# air.net
KiCad netlist of a schematic drawn in Altium Designer
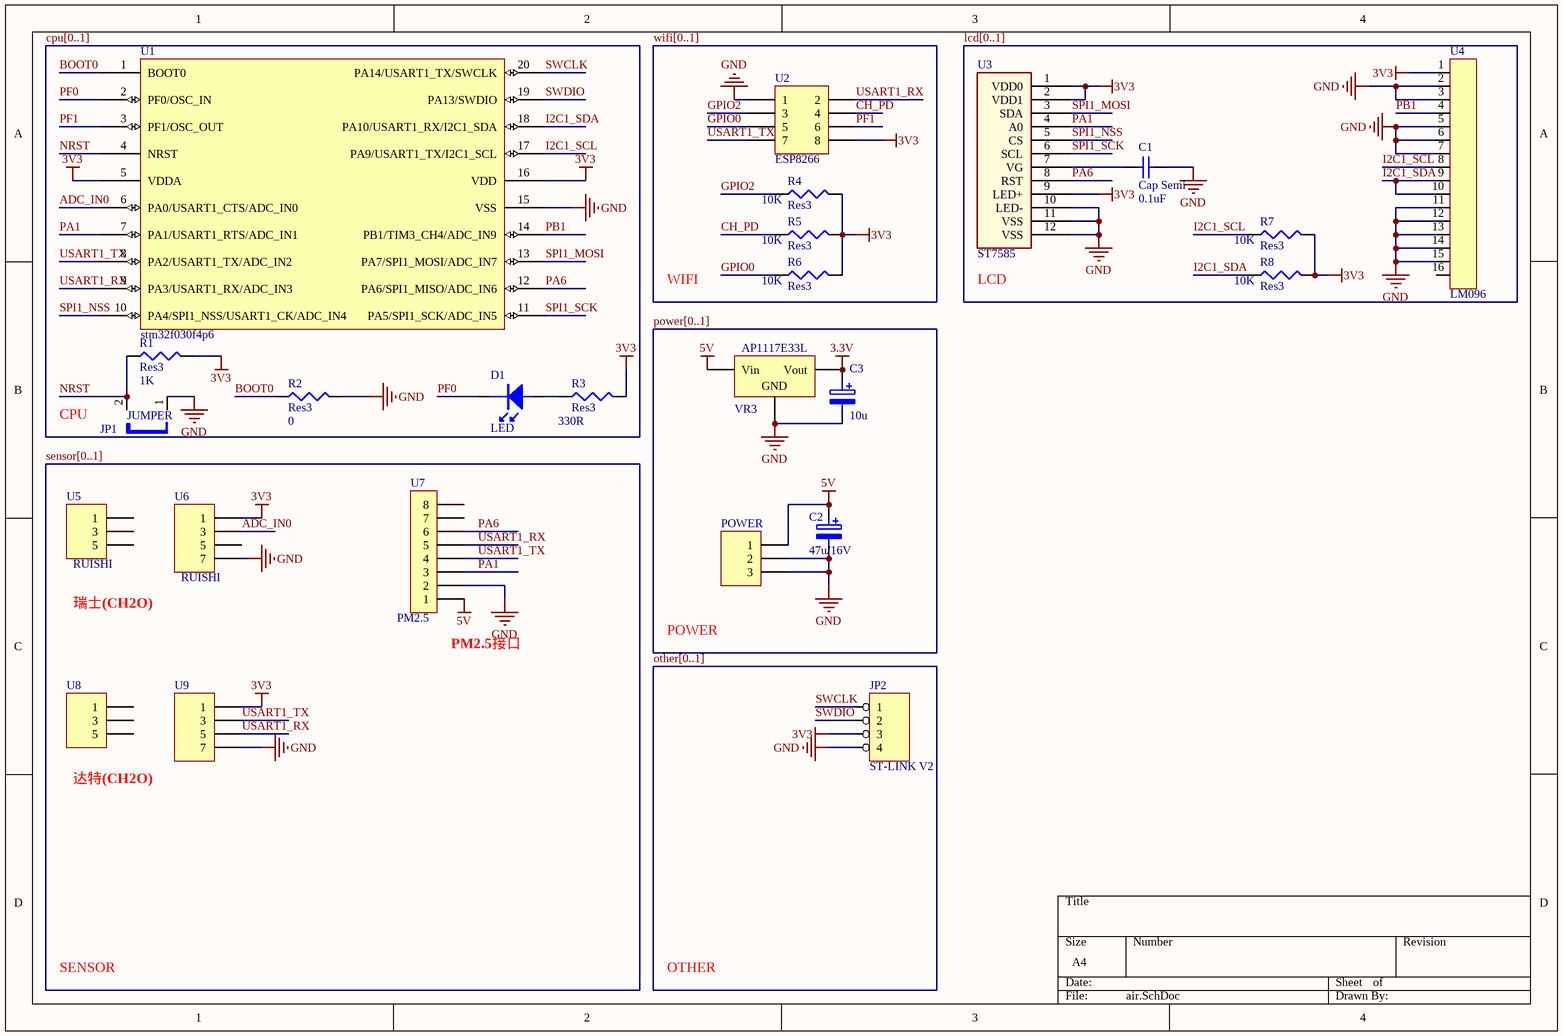
[diagram p0: air.SchDoc]

(export (version "E")
  (design (tool "Eeschema 10.0.6"))
  (components
    (comp (ref "C1")
      (value "Cap Semi")
      (footprint "LC-0603_C")
      (description "Capacitor (Semiconductor SIM Model)")
      (fields (field (name "ALTIUM_VALUE") "0.1uF") (field (name "PUBLISHER") "Altium Limited"))
      (libsource (lib "Miscellaneous Devices") (part "Cap Semi"))
    )
    (comp (ref "C2") (value "47u/16V") (footprint "LC-CASE-B_3528") (libsource (lib "*") (part "ELECTRO2")))
    (comp (ref "C3") (value "10u") (footprint "LC-CASE-B_3528") (libsource (lib "*") (part "ELECTRO2")))
    (comp (ref "D1")
      (value "LED")
      (footprint "LC-0603_LED_S1")
      (libsource (lib "BASIC Devices") (part "LED"))
    )
    (comp (ref "JP1")
      (value "JUMPER")
      (footprint "HDR1X2")
      (description "Jumper")
      (libsource (lib "BASIC Devices") (part "JUMPER"))
    )
    (comp (ref "JP2")
      (value "ST-LINK V2")
      (footprint "HDR1x4")
      (description "4 Pin Header")
      (libsource (lib "BASIC Devices") (part "4 HEADER"))
    )
    (comp (ref "POWER")
      (value "Header 3")
      (footprint "POWER-B")
      (description "Header, 3-Pin")
      (fields (field (name "PUBLISHER") "Altium Limited"))
      (libsource (lib "在线监测仪-01") (part "Header 3"))
    )
    (comp (ref "R1")
      (value "Res3")
      (footprint "LC-0603_R")
      (description "Resistor")
      (fields (field (name "ALTIUM_VALUE") "1K") (field (name "PUBLISHER") "Altium Limited"))
      (libsource (lib "Miscellaneous Devices") (part "Res3"))
    )
    (comp (ref "R2")
      (value "Res3")
      (footprint "LC-0603_R")
      (description "Resistor")
      (fields (field (name "ALTIUM_VALUE") "0") (field (name "PUBLISHER") "Altium Limited"))
      (libsource (lib "Miscellaneous Devices") (part "Res3"))
    )
    (comp (ref "R3")
      (value "Res3")
      (footprint "LC-0603_R")
      (description "Resistor")
      (fields (field (name "ALTIUM_VALUE") "330R") (field (name "PUBLISHER") "Altium Limited"))
      (libsource (lib "Miscellaneous Devices") (part "Res3"))
    )
    (comp (ref "R4")
      (value "Res3")
      (footprint "LC-0603_R")
      (description "Resistor")
      (fields (field (name "ALTIUM_VALUE") "10K") (field (name "PUBLISHER") "Altium Limited"))
      (libsource (lib "Miscellaneous Devices") (part "Res3"))
    )
    (comp (ref "R5")
      (value "Res3")
      (footprint "LC-0603_R")
      (description "Resistor")
      (fields (field (name "ALTIUM_VALUE") "10K") (field (name "PUBLISHER") "Altium Limited"))
      (libsource (lib "Miscellaneous Devices") (part "Res3"))
    )
    (comp (ref "R6")
      (value "Res3")
      (footprint "LC-0603_R")
      (description "Resistor")
      (fields (field (name "ALTIUM_VALUE") "10K") (field (name "PUBLISHER") "Altium Limited"))
      (libsource (lib "Miscellaneous Devices") (part "Res3"))
    )
    (comp (ref "R7")
      (value "Res3")
      (footprint "LC-0603_R")
      (description "Resistor")
      (fields (field (name "ALTIUM_VALUE") "10K") (field (name "PUBLISHER") "Altium Limited"))
      (libsource (lib "Miscellaneous Devices") (part "Res3"))
    )
    (comp (ref "R8")
      (value "Res3")
      (footprint "LC-0603_R")
      (description "Resistor")
      (fields (field (name "ALTIUM_VALUE") "10K") (field (name "PUBLISHER") "Altium Limited"))
      (libsource (lib "Miscellaneous Devices") (part "Res3"))
    )
    (comp (ref "U1")
      (value "stm32f030f4p6")
      (footprint "LC-TSSOP-20")
      (libsource (lib "*") (part "stm32f030f4p6"))
    )
    (comp (ref "U2")
      (value "ESP8266")
      (footprint "HDR2X4")
      (description "Header, 4-Pin, Dual row")
      (fields (field (name "PUBLISHER") "Altium Limited"))
      (libsource (lib "Miscellaneous Connectors") (part "Header 4X2"))
    )
    (comp (ref "U3") (value "ST7585") (footprint "ST7585") (libsource (lib "ST7585") (part "ST7585")))
    (comp (ref "U4") (value "LM096") (footprint "IDC16") (libsource (lib "BASIC Devices") (part "16PIN")))
    (comp (ref "U5")
      (value "RUISHI")
      (footprint "HDR2X3")
      (description "Header, 6-Pin")
      (fields (field (name "PUBLISHER") "Altium Limited"))
      (libsource (lib "在线监测仪-02") (part "Header 33"))
    )
    (comp (ref "U6")
      (value "RUISHI")
      (footprint "HDR2X4")
      (description "Header, 8-Pin")
      (fields (field (name "PUBLISHER") "Altium Limited"))
      (libsource (lib "在线监测仪-02") (part "Header 44"))
    )
    (comp (ref "U7")
      (value "PM2.5")
      (footprint "MHDR1x8")
      (description "Connector")
      (libsource (lib "在线监测仪") (part "8PIN"))
    )
    (comp (ref "U8")
      (value "~")
      (footprint "HDR2X3")
      (description "Header, 6-Pin")
      (fields (field (name "PUBLISHER") "Altium Limited"))
      (libsource (lib "在线监测仪-02") (part "Header 33"))
    )
    (comp (ref "U9")
      (value "Header 4")
      (footprint "HDR2X4")
      (description "Header, 8-Pin")
      (fields (field (name "PUBLISHER") "Altium Limited"))
      (libsource (lib "在线监测仪-02") (part "Header 44"))
    )
    (comp (ref "VR3")
      (value "AP1117E33L")
      (footprint "LC-SOT-223")
      (description "Voltage Regulator")
      (fields (field (name "PUBLISHER") "Altium Limited"))
      (libsource (lib "在线监测仪-02") (part "Volt Reg"))
    )
  )
  (nets
    (net (code "13") (name "/ADC_IN0") (class "Default")
      (node (ref "U1") (pin "6") (pinfunction "PA0/USART1_CTS/ADC_IN0_6") (pintype "bidirectional"))
      (node (ref "U6") (pin "3") (pinfunction "3_3") (pintype "passive"))
    )
    (net (code "14") (name "/BOOT0") (class "Default")
      (node (ref "R2") (pin "1") (pinfunction "1_1") (pintype "passive"))
      (node (ref "U1") (pin "1") (pinfunction "BOOT0_1") (pintype "passive"))
    )
    (net (code "15") (name "/CH_PD") (class "Default")
      (node (ref "R5") (pin "1") (pinfunction "1_1") (pintype "passive"))
      (node (ref "U2") (pin "4") (pinfunction "4_4") (pintype "passive"))
    )
    (net (code "16") (name "/GPIO0") (class "Default")
      (node (ref "R6") (pin "1") (pinfunction "1_1") (pintype "passive"))
      (node (ref "U2") (pin "5") (pinfunction "5_5") (pintype "passive"))
    )
    (net (code "17") (name "/GPIO2") (class "Default")
      (node (ref "R4") (pin "1") (pinfunction "1_1") (pintype "passive"))
      (node (ref "U2") (pin "3") (pinfunction "3_3") (pintype "passive"))
    )
    (net (code "18") (name "/I2C1_SCL") (class "Default")
      (node (ref "R7") (pin "1") (pinfunction "1_1") (pintype "passive"))
      (node (ref "U1") (pin "17") (pinfunction "PA9/USART1_TX/I2C1_SCL_17") (pintype "bidirectional"))
      (node (ref "U4") (pin "8") (pinfunction "8_8") (pintype "passive"))
    )
    (net (code "19") (name "/I2C1_SDA") (class "Default")
      (node (ref "R8") (pin "1") (pinfunction "1_1") (pintype "passive"))
      (node (ref "U1") (pin "18") (pinfunction "PA10/USART1_RX/I2C1_SDA_18") (pintype "bidirectional"))
      (node (ref "U4") (pin "10") (pinfunction "10_10") (pintype "passive"))
      (node (ref "U4") (pin "9") (pinfunction "9_9") (pintype "passive"))
    )
    (net (code "20") (name "/NRST") (class "Default")
      (node (ref "JP1") (pin "2") (pinfunction "2_2") (pintype "passive"))
      (node (ref "R1") (pin "1") (pinfunction "1_1") (pintype "passive"))
      (node (ref "U1") (pin "4") (pinfunction "NRST_4") (pintype "passive"))
    )
    (net (code "21") (name "/PA1") (class "Default")
      (node (ref "U1") (pin "7") (pinfunction "PA1/USART1_RTS/ADC_IN1_7") (pintype "bidirectional"))
      (node (ref "U3") (pin "4") (pinfunction "A0_4") (pintype "passive"))
      (node (ref "U7") (pin "3") (pinfunction "3_3") (pintype "passive"))
    )
    (net (code "22") (name "/PA6") (class "Default")
      (node (ref "U1") (pin "12") (pinfunction "PA6/SPI1_MISO/ADC_IN6_12") (pintype "bidirectional"))
      (node (ref "U3") (pin "8") (pinfunction "RST_8") (pintype "passive"))
      (node (ref "U7") (pin "6") (pinfunction "6_6") (pintype "passive"))
    )
    (net (code "23") (name "/PB1") (class "Default")
      (node (ref "U1") (pin "14") (pinfunction "PB1/TIM3_CH4/ADC_IN9_14") (pintype "bidirectional"))
      (node (ref "U4") (pin "4") (pinfunction "4_4") (pintype "passive"))
    )
    (net (code "24") (name "/PF0") (class "Default")
      (node (ref "D1") (pin "K") (pinfunction "K_K") (pintype "passive"))
      (node (ref "U1") (pin "2") (pinfunction "PF0/OSC_IN_2") (pintype "bidirectional"))
    )
    (net (code "25") (name "/PF1") (class "Default")
      (node (ref "U1") (pin "3") (pinfunction "PF1/OSC_OUT_3") (pintype "bidirectional"))
      (node (ref "U2") (pin "6") (pinfunction "6_6") (pintype "passive"))
    )
    (net (code "26") (name "/SPI1_MOSI") (class "Default")
      (node (ref "U1") (pin "13") (pinfunction "PA7/SPI1_MOSI/ADC_IN7_13") (pintype "bidirectional"))
      (node (ref "U3") (pin "3") (pinfunction "SDA_3") (pintype "passive"))
    )
    (net (code "27") (name "/SPI1_NSS") (class "Default")
      (node (ref "U1") (pin "10") (pinfunction "PA4/SPI1_NSS/USART1_CK/ADC_IN4_10") (pintype "bidirectional"))
      (node (ref "U3") (pin "5") (pinfunction "CS_5") (pintype "passive"))
    )
    (net (code "28") (name "/SPI1_SCK") (class "Default")
      (node (ref "U1") (pin "11") (pinfunction "PA5/SPI1_SCK/ADC_IN5_11") (pintype "bidirectional"))
      (node (ref "U3") (pin "6") (pinfunction "SCL_6") (pintype "passive"))
    )
    (net (code "29") (name "/SWCLK") (class "Default")
      (node (ref "JP2") (pin "1") (pinfunction "1_1") (pintype "passive"))
      (node (ref "U1") (pin "20") (pinfunction "PA14/USART1_TX/SWCLK_20") (pintype "bidirectional"))
    )
    (net (code "30") (name "/SWDIO") (class "Default")
      (node (ref "JP2") (pin "2") (pinfunction "2_2") (pintype "passive"))
      (node (ref "U1") (pin "19") (pinfunction "PA13/SWDIO_19") (pintype "bidirectional"))
    )
    (net (code "31") (name "/USART1_RX") (class "Default")
      (node (ref "U1") (pin "9") (pinfunction "PA3/USART1_RX/ADC_IN3_9") (pintype "bidirectional"))
      (node (ref "U2") (pin "2") (pinfunction "2_2") (pintype "passive"))
      (node (ref "U7") (pin "5") (pinfunction "5_5") (pintype "passive"))
      (node (ref "U9") (pin "5") (pinfunction "5_5") (pintype "passive"))
    )
    (net (code "32") (name "/USART1_TX") (class "Default")
      (node (ref "U1") (pin "8") (pinfunction "PA2/USART1_TX/ADC_IN2_8") (pintype "bidirectional"))
      (node (ref "U2") (pin "7") (pinfunction "7_7") (pintype "passive"))
      (node (ref "U7") (pin "4") (pinfunction "4_4") (pintype "passive"))
      (node (ref "U9") (pin "3") (pinfunction "3_3") (pintype "passive"))
    )
    (net (code "39") (name "3.3V") (class "Default")
      (node (ref "C3") (pin "1") (pintype "passive"))
      (node (ref "VR3") (pin "2") (pinfunction "Vout_2") (pintype "passive"))
    )
    (net (code "40") (name "3V3") (class "Default")
      (node (ref "JP2") (pin "3") (pinfunction "3_3") (pintype "passive"))
      (node (ref "R1") (pin "2") (pinfunction "2_2") (pintype "passive"))
      (node (ref "R3") (pin "2") (pinfunction "2_2") (pintype "passive"))
      (node (ref "R4") (pin "2") (pinfunction "2_2") (pintype "passive"))
      (node (ref "R5") (pin "2") (pinfunction "2_2") (pintype "passive"))
      (node (ref "R6") (pin "2") (pinfunction "2_2") (pintype "passive"))
      (node (ref "R7") (pin "2") (pinfunction "2_2") (pintype "passive"))
      (node (ref "R8") (pin "2") (pinfunction "2_2") (pintype "passive"))
      (node (ref "U1") (pin "16") (pinfunction "VDD_16") (pintype "power_in"))
      (node (ref "U1") (pin "5") (pinfunction "VDDA_5") (pintype "power_in"))
      (node (ref "U2") (pin "8") (pinfunction "8_8") (pintype "passive"))
      (node (ref "U3") (pin "1") (pinfunction "VDD0_1") (pintype "passive"))
      (node (ref "U3") (pin "2") (pinfunction "VDD1_2") (pintype "passive"))
      (node (ref "U3") (pin "9") (pinfunction "LED+_9") (pintype "passive"))
      (node (ref "U4") (pin "1") (pinfunction "1_1") (pintype "passive"))
      (node (ref "U6") (pin "1") (pinfunction "1_1") (pintype "passive"))
      (node (ref "U9") (pin "1") (pinfunction "1_1") (pintype "passive"))
    )
    (net (code "41") (name "5V") (class "Default")
      (node (ref "C2") (pin "1") (pintype "passive"))
      (node (ref "POWER") (pin "1") (pinfunction "1_1") (pintype "passive"))
      (node (ref "U7") (pin "1") (pinfunction "1_1") (pintype "passive"))
      (node (ref "VR3") (pin "3") (pinfunction "Vin_3") (pintype "passive"))
    )
    (net (code "42") (name "GND") (class "Default")
      (node (ref "C1") (pin "2") (pinfunction "2_2") (pintype "passive"))
      (node (ref "C2") (pin "2") (pintype "passive"))
      (node (ref "C3") (pin "2") (pintype "passive"))
      (node (ref "JP1") (pin "1") (pinfunction "1_1") (pintype "passive"))
      (node (ref "JP2") (pin "4") (pinfunction "4_4") (pintype "passive"))
      (node (ref "POWER") (pin "2") (pinfunction "2_2") (pintype "passive"))
      (node (ref "POWER") (pin "3") (pinfunction "3_3") (pintype "passive"))
      (node (ref "R2") (pin "2") (pinfunction "2_2") (pintype "passive"))
      (node (ref "U1") (pin "15") (pinfunction "VSS_15") (pintype "power_in"))
      (node (ref "U2") (pin "1") (pinfunction "1_1") (pintype "passive"))
      (node (ref "U3") (pin "10") (pinfunction "LED-_10") (pintype "passive"))
      (node (ref "U3") (pin "11") (pinfunction "VSS_11") (pintype "passive"))
      (node (ref "U3") (pin "12") (pinfunction "VSS_12") (pintype "passive"))
      (node (ref "U4") (pin "11") (pinfunction "11_11") (pintype "passive"))
      (node (ref "U4") (pin "12") (pinfunction "12_12") (pintype "passive"))
      (node (ref "U4") (pin "13") (pinfunction "13_13") (pintype "passive"))
      (node (ref "U4") (pin "14") (pinfunction "14_14") (pintype "passive"))
      (node (ref "U4") (pin "15") (pinfunction "15_15") (pintype "passive"))
      (node (ref "U4") (pin "2") (pinfunction "2_2") (pintype "passive"))
      (node (ref "U4") (pin "3") (pinfunction "3_3") (pintype "passive"))
      (node (ref "U4") (pin "5") (pinfunction "5_5") (pintype "passive"))
      (node (ref "U4") (pin "6") (pinfunction "6_6") (pintype "passive"))
      (node (ref "U4") (pin "7") (pinfunction "7_7") (pintype "passive"))
      (node (ref "U6") (pin "7") (pinfunction "7_7") (pintype "passive"))
      (node (ref "U7") (pin "2") (pinfunction "2_2") (pintype "passive"))
      (node (ref "U9") (pin "7") (pinfunction "7_7") (pintype "passive"))
      (node (ref "VR3") (pin "1") (pinfunction "GND_1") (pintype "passive"))
    )
    (net (code "43") (name "Net-(D1-PadA)") (class "Default")
      (node (ref "D1") (pin "A") (pinfunction "A_A") (pintype "passive"))
      (node (ref "R3") (pin "1") (pinfunction "1_1") (pintype "passive"))
    )
    (net (code "44") (name "Net-(U3-VG)") (class "Default")
      (node (ref "C1") (pin "1") (pinfunction "1_1") (pintype "passive"))
      (node (ref "U3") (pin "7") (pinfunction "VG_7") (pintype "passive"))
    )
    (net (code "45") (name "unconnected-(U4-Pad16)") (class "Default")
      (node (ref "U4") (pin "16") (pinfunction "16_16") (pintype "passive"))
    )
    (net (code "46") (name "unconnected-(U5-Pad1)") (class "Default")
      (node (ref "U5") (pin "1") (pinfunction "1_1") (pintype "passive"))
    )
    (net (code "47") (name "unconnected-(U5-Pad2)") (class "Default")
      (node (ref "U5") (pin "2") (pinfunction "2_2") (pintype "passive"))
    )
    (net (code "48") (name "unconnected-(U5-Pad3)") (class "Default")
      (node (ref "U5") (pin "3") (pinfunction "3_3") (pintype "passive"))
    )
    (net (code "49") (name "unconnected-(U5-Pad4)") (class "Default")
      (node (ref "U5") (pin "4") (pinfunction "4_4") (pintype "passive"))
    )
    (net (code "50") (name "unconnected-(U5-Pad5)") (class "Default")
      (node (ref "U5") (pin "5") (pinfunction "5_5") (pintype "passive"))
    )
    (net (code "51") (name "unconnected-(U5-Pad6)") (class "Default")
      (node (ref "U5") (pin "6") (pinfunction "6_6") (pintype "passive"))
    )
    (net (code "52") (name "unconnected-(U6-Pad2)") (class "Default")
      (node (ref "U6") (pin "2") (pinfunction "2_2") (pintype "passive"))
    )
    (net (code "53") (name "unconnected-(U6-Pad4)") (class "Default")
      (node (ref "U6") (pin "4") (pinfunction "4_4") (pintype "passive"))
    )
    (net (code "54") (name "unconnected-(U6-Pad5)") (class "Default")
      (node (ref "U6") (pin "5") (pinfunction "5_5") (pintype "passive"))
    )
    (net (code "55") (name "unconnected-(U6-Pad6)") (class "Default")
      (node (ref "U6") (pin "6") (pinfunction "6_6") (pintype "passive"))
    )
    (net (code "56") (name "unconnected-(U6-Pad8)") (class "Default")
      (node (ref "U6") (pin "8") (pinfunction "8_8") (pintype "passive"))
    )
    (net (code "57") (name "unconnected-(U7-Pad7)") (class "Default")
      (node (ref "U7") (pin "7") (pinfunction "7_7") (pintype "passive"))
    )
    (net (code "58") (name "unconnected-(U7-Pad8)") (class "Default")
      (node (ref "U7") (pin "8") (pinfunction "8_8") (pintype "passive"))
    )
    (net (code "59") (name "unconnected-(U8-Pad1)") (class "Default")
      (node (ref "U8") (pin "1") (pinfunction "1_1") (pintype "passive"))
    )
    (net (code "60") (name "unconnected-(U8-Pad2)") (class "Default")
      (node (ref "U8") (pin "2") (pinfunction "2_2") (pintype "passive"))
    )
    (net (code "61") (name "unconnected-(U8-Pad3)") (class "Default")
      (node (ref "U8") (pin "3") (pinfunction "3_3") (pintype "passive"))
    )
    (net (code "62") (name "unconnected-(U8-Pad4)") (class "Default")
      (node (ref "U8") (pin "4") (pinfunction "4_4") (pintype "passive"))
    )
    (net (code "63") (name "unconnected-(U8-Pad5)") (class "Default")
      (node (ref "U8") (pin "5") (pinfunction "5_5") (pintype "passive"))
    )
    (net (code "64") (name "unconnected-(U8-Pad6)") (class "Default")
      (node (ref "U8") (pin "6") (pinfunction "6_6") (pintype "passive"))
    )
    (net (code "65") (name "unconnected-(U9-Pad2)") (class "Default")
      (node (ref "U9") (pin "2") (pinfunction "2_2") (pintype "passive"))
    )
    (net (code "66") (name "unconnected-(U9-Pad4)") (class "Default")
      (node (ref "U9") (pin "4") (pinfunction "4_4") (pintype "passive"))
    )
    (net (code "67") (name "unconnected-(U9-Pad6)") (class "Default")
      (node (ref "U9") (pin "6") (pinfunction "6_6") (pintype "passive"))
    )
    (net (code "68") (name "unconnected-(U9-Pad8)") (class "Default")
      (node (ref "U9") (pin "8") (pinfunction "8_8") (pintype "passive"))
    )
  )
)
